# 09_CAN.net
KiCad netlist of a schematic drawn in Altium Designer
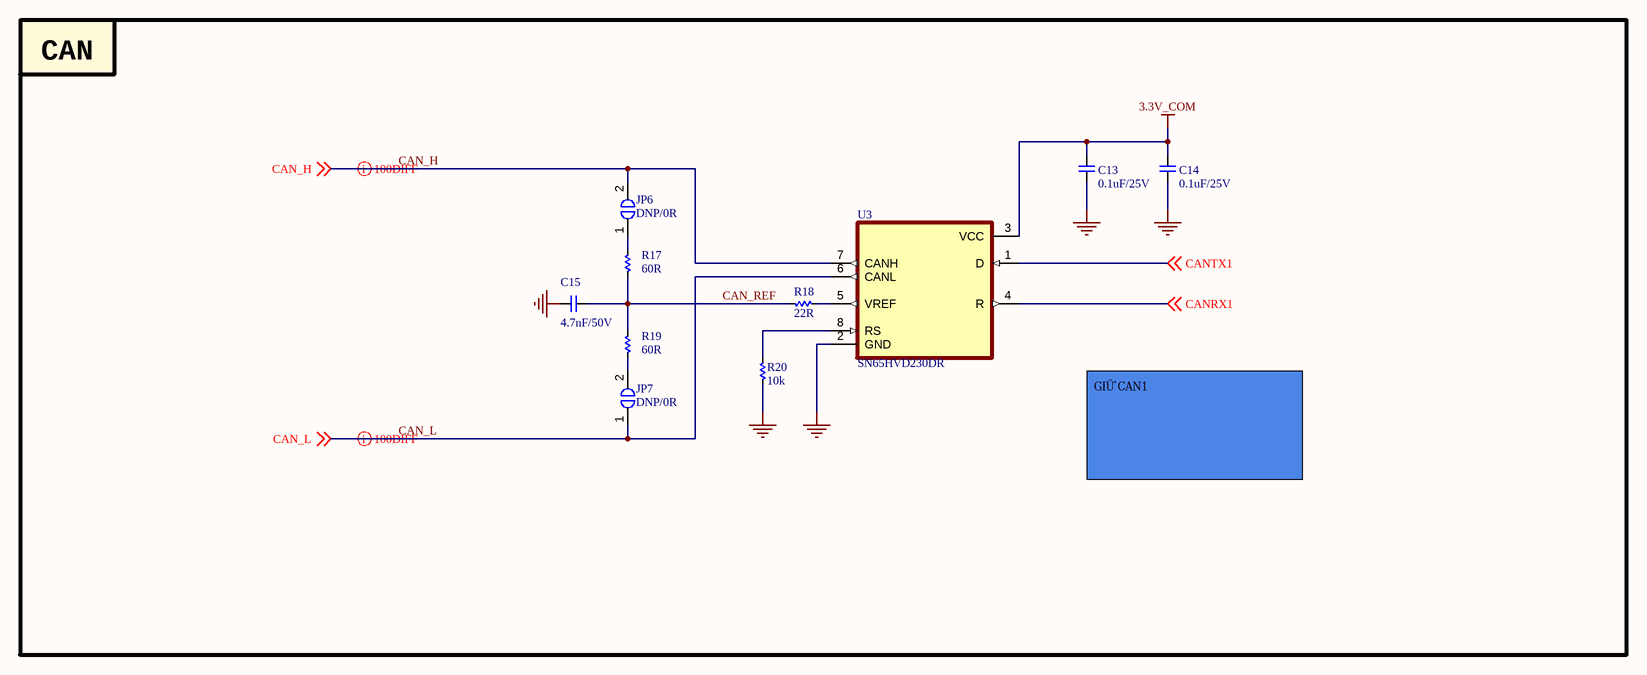
[diagram p0: 09_CAN.SchDoc]

(export (version "E")
  (design (tool "Eeschema 10.0.6"))
  (components
    (comp (ref "C13")
      (value "0.1uF/25V")
      (footprint "CAP_C_1005X60")
      (description "CAP")
      (libsource (lib "LABLIB") (part "_CAP_C_2"))
    )
    (comp (ref "C14")
      (value "0.1uF/25V")
      (footprint "CAP_C_1005X60")
      (description "CAP")
      (libsource (lib "LABLIB") (part "_CAP_C_2"))
    )
    (comp (ref "C15")
      (value "4.7nF/50V")
      (footprint "CAP_C_1608X80")
      (description "CAP")
      (libsource (lib "LABLIB") (part "_CAP_C_2"))
    )
    (comp (ref "JP6")
      (value "DNP/0R")
      (footprint "RES_C_1608X60")
      (libsource (lib "LABLIB") (part "JUMPER_1_1"))
    )
    (comp (ref "JP7")
      (value "DNP/0R")
      (footprint "RES_C_1608X60")
      (libsource (lib "LABLIB") (part "JUMPER_1_1"))
    )
    (comp (ref "R17")
      (value "60R")
      (footprint "RES_C_1005X40")
      (description "RES")
      (libsource (lib "LABLIB") (part "_RES_B_2"))
    )
    (comp (ref "R18")
      (value "22R")
      (footprint "RES_C_1005X40")
      (description "RES")
      (libsource (lib "LABLIB") (part "_RES_B_2"))
    )
    (comp (ref "R19")
      (value "60R")
      (footprint "RES_C_1005X40")
      (description "RES")
      (libsource (lib "LABLIB") (part "_RES_B_2"))
    )
    (comp (ref "R20")
      (value "10k")
      (footprint "RES_C_1005X40")
      (description "RES")
      (libsource (lib "LABLIB") (part "_RES_B_2"))
    )
    (comp (ref "U3")
      (value "SN65HVD230DR")
      (footprint "SOIC127P600X175-8N")
      (description "3.3 V CAN Transceiver with Standby Mode")
      (fields (field (name "MF") "Texas Instruments"))
      (libsource (lib "BEE-1012 PAY-EXP_V110") (part "SN65HVD230DR"))
    )
  )
  (nets
    (net (code "1") (name "/CAN_REF") (class "Default")
      (node (ref "C15") (pin "1") (pinfunction "1_1") (pintype "passive"))
      (node (ref "R17") (pin "1") (pinfunction "1_1") (pintype "passive"))
      (node (ref "R18") (pin "1") (pinfunction "1_1") (pintype "passive"))
      (node (ref "R19") (pin "2") (pinfunction "2_2") (pintype "passive"))
    )
    (net (code "2") (name "3.3V_COM") (class "Default")
      (node (ref "C13") (pin "1") (pinfunction "1_1") (pintype "passive"))
      (node (ref "C14") (pin "1") (pinfunction "1_1") (pintype "passive"))
      (node (ref "U3") (pin "3") (pinfunction "VCC_3") (pintype "power_in"))
    )
    (net (code "3") (name "CANRX1") (class "Default")
      (node (ref "U3") (pin "4") (pinfunction "R_4") (pintype "output"))
    )
    (net (code "4") (name "CANTX1") (class "Default")
      (node (ref "U3") (pin "1") (pinfunction "D_1") (pintype "input"))
    )
    (net (code "5") (name "CAN_H") (class "Default")
      (node (ref "JP6") (pin "2") (pinfunction "2_2") (pintype "passive"))
      (node (ref "U3") (pin "7") (pinfunction "CANH_7") (pintype "output"))
    )
    (net (code "6") (name "CAN_L") (class "Default")
      (node (ref "JP7") (pin "1") (pinfunction "1_1") (pintype "passive"))
      (node (ref "U3") (pin "6") (pinfunction "CANL_6") (pintype "output"))
    )
    (net (code "7") (name "GND") (class "Default")
      (node (ref "C13") (pin "2") (pinfunction "2_2") (pintype "passive"))
      (node (ref "C14") (pin "2") (pinfunction "2_2") (pintype "passive"))
      (node (ref "C15") (pin "2") (pinfunction "2_2") (pintype "passive"))
      (node (ref "R20") (pin "1") (pinfunction "1_1") (pintype "passive"))
      (node (ref "U3") (pin "2") (pinfunction "GND_2") (pintype "power_in"))
    )
    (net (code "8") (name "Net-(JP6-Pad1)") (class "Default")
      (node (ref "JP6") (pin "1") (pinfunction "1_1") (pintype "passive"))
      (node (ref "R17") (pin "2") (pinfunction "2_2") (pintype "passive"))
    )
    (net (code "9") (name "Net-(JP7-Pad2)") (class "Default")
      (node (ref "JP7") (pin "2") (pinfunction "2_2") (pintype "passive"))
      (node (ref "R19") (pin "1") (pinfunction "1_1") (pintype "passive"))
    )
    (net (code "10") (name "Net-(U3-RS)") (class "Default")
      (node (ref "R20") (pin "2") (pinfunction "2_2") (pintype "passive"))
      (node (ref "U3") (pin "8") (pinfunction "RS_8") (pintype "input"))
    )
    (net (code "11") (name "Net-(U3-VREF)") (class "Default")
      (node (ref "R18") (pin "2") (pinfunction "2_2") (pintype "passive"))
      (node (ref "U3") (pin "5") (pinfunction "VREF_5") (pintype "output"))
    )
  )
)
